# cc2650.net
KiCad netlist of a schematic drawn in EAGLE
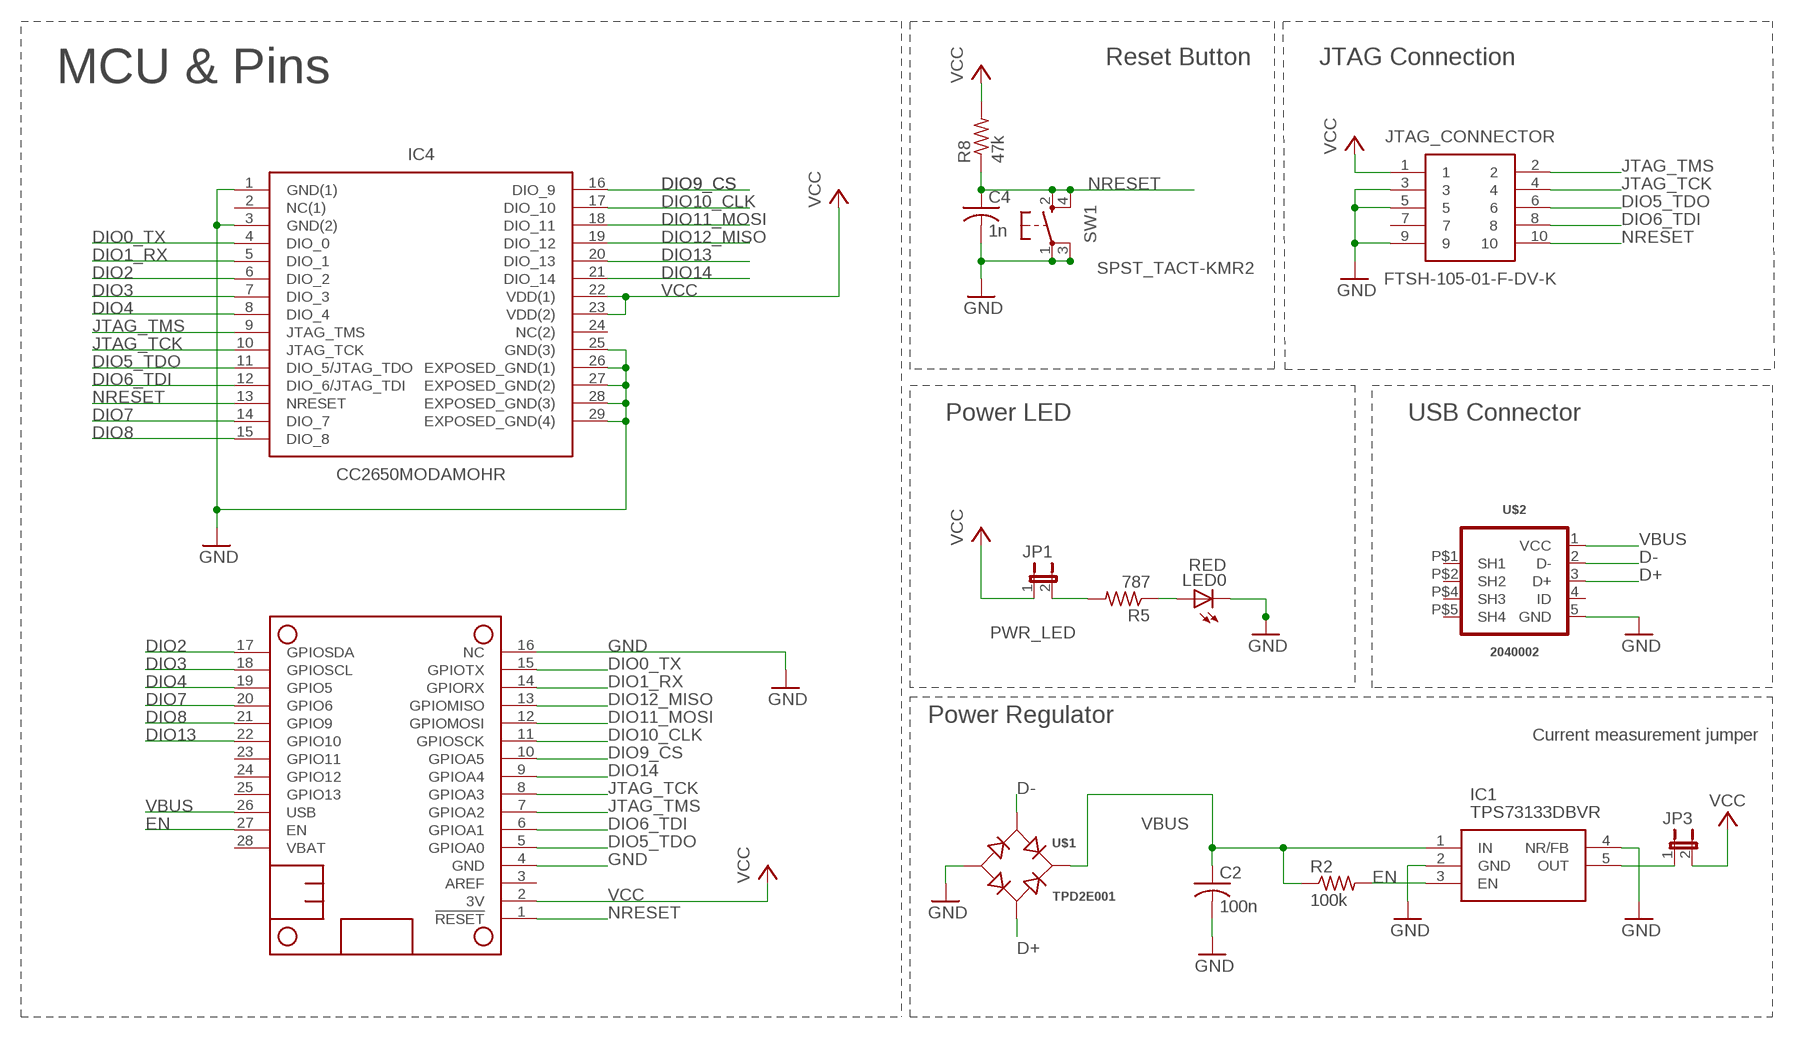
[diagram p0: schematic, sheet 1]
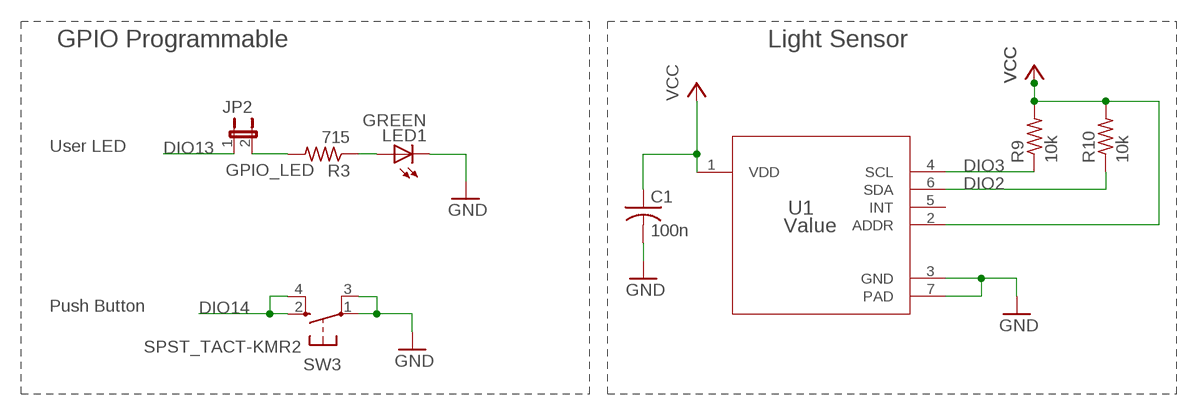
[diagram p1: schematic, sheet 2]

(export (version "E")
  (design (tool "Eeschema 10.0.6"))
  (components
    (comp (ref "C1")
      (value "100n")
      (footprint "eagle-import:C0805")
      (fields (field (name "MPN") "C0805C105K5RACTU"))
      (libsource (lib "eagle-import") (part "C-USC0805"))
    )
    (comp (ref "JP2")
      (value "GPIO_LED")
      (footprint "eagle-import:JP1M")
      (fields (field (name "MPN") "2211S-02G"))
      (libsource (lib "eagle-import") (part "JP1M"))
    )
    (comp (ref "LED1")
      (value "GREEN")
      (footprint "eagle-import:CHIPLED_0603")
      (libsource (lib "eagle-import") (part "LEDCHIPLED_0603"))
    )
    (comp (ref "R3")
      (value "715")
      (footprint "eagle-import:R0603")
      (fields (field (name "MPN") "RC0603JR-07100KL"))
      (libsource (lib "eagle-import") (part "R-US_R0603"))
    )
    (comp (ref "R9")
      (value "10k")
      (footprint "eagle-import:R1206")
      (libsource (lib "eagle-import") (part "R-US_R1206"))
    )
    (comp (ref "R10")
      (value "10k")
      (footprint "eagle-import:R1206")
      (libsource (lib "eagle-import") (part "R-US_R1206"))
    )
    (comp (ref "SW3")
      (value "SPST_TACT-KMR2")
      (footprint "eagle-import:KMR2")
      (fields (field (name "MPN") "KMR241G LFS"))
      (libsource (lib "eagle-import") (part "SPST_TACT-KMR2"))
    )
    (comp (ref "U1")
      (value "Value")
      (footprint "eagle-import:DNP0006A")
      (fields (field (name "MANUFACTURER") "Texas Instruments") (field (name "PARTNUMBER") "OPT3001DNP"))
      (libsource (lib "eagle-import") (part "OPT3001DNPR"))
    )
    (comp (ref "C2")
      (value "100n")
      (footprint "eagle-import:C1206")
      (libsource (lib "eagle-import") (part "C-USC1206"))
    )
    (comp (ref "C4")
      (value "1n")
      (footprint "eagle-import:C1206")
      (libsource (lib "eagle-import") (part "C-USC1206"))
    )
    (comp (ref "IC1")
      (value "TPS73133DBVR")
      (footprint "eagle-import:SOT95P280X145-5N")
      (fields (field (name "RS_PART_NUMBER") "6613970"))
      (libsource (lib "eagle-import") (part "TPS73133DBVR"))
    )
    (comp (ref "IC4")
      (value "CC2650MODAMOHR")
      (footprint "eagle-import:MOH0029A")
      (libsource (lib "eagle-import") (part "CC2650MODAMOHR"))
    )
    (comp (ref "JP1")
      (value "PWR_LED")
      (footprint "eagle-import:JP1M")
      (fields (field (name "MPN") "2211S-02G"))
      (libsource (lib "eagle-import") (part "JP1M"))
    )
    (comp (ref "JP3")
      (value "PWR_LED")
      (footprint "eagle-import:JP1M")
      (fields (field (name "MPN") "2211S-02G"))
      (libsource (lib "eagle-import") (part "JP1M"))
    )
    (comp (ref "JTAG_CONNECTOR")
      (value "FTSH-105-01-F-DV-K")
      (footprint "eagle-import:SAMTEC_FTSH-105-01-L-DV")
      (libsource (lib "eagle-import") (part "FTSH-105-01-F-DV-K"))
    )
    (comp (ref "LED0")
      (value "RED")
      (footprint "eagle-import:CHIPLED_0603")
      (libsource (lib "eagle-import") (part "LEDCHIPLED_0603"))
    )
    (comp (ref "MS1")
      (value "FEATHERWING_NODIM")
      (footprint "eagle-import:FEATHERWING_DIM")
      (libsource (lib "eagle-import") (part "FEATHERWING_NODIM"))
    )
    (comp (ref "R2")
      (value "100k")
      (footprint "eagle-import:R1206")
      (libsource (lib "eagle-import") (part "R-US_R1206"))
    )
    (comp (ref "R5")
      (value "787")
      (footprint "eagle-import:R0603")
      (fields (field (name "MPN") "RC0603JR-07100KL"))
      (libsource (lib "eagle-import") (part "R-US_R0603"))
    )
    (comp (ref "R8")
      (value "47k")
      (footprint "eagle-import:R1206")
      (libsource (lib "eagle-import") (part "R-US_R1206"))
    )
    (comp (ref "SW1")
      (value "SPST_TACT-KMR2")
      (footprint "eagle-import:KMR2")
      (fields (field (name "MPN") "KMR241G LFS"))
      (libsource (lib "eagle-import") (part "SPST_TACT-KMR2"))
    )
    (comp (ref "U$1")
      (value "TPD2E001")
      (footprint "eagle-import:SOT-143")
      (libsource (lib "eagle-import") (part "TPD2E001"))
    )
    (comp (ref "U$2")
      (value "2040002")
      (footprint "eagle-import:2040002")
      (libsource (lib "eagle-import") (part "2040002"))
    )
  )
  (nets
    (net (code "1") (name "D+") (class "Default")
      (node (ref "U$1") (pin "3") (pinfunction "AC2_3") (pintype "passive"))
      (node (ref "U$2") (pin "3") (pinfunction "D+_3") (pintype "bidirectional"))
    )
    (net (code "2") (name "D-") (class "Default")
      (node (ref "U$1") (pin "2") (pinfunction "AC1_2") (pintype "passive"))
      (node (ref "U$2") (pin "2") (pinfunction "D-_2") (pintype "bidirectional"))
    )
    (net (code "3") (name "DIO0_TX") (class "Default")
      (node (ref "IC4") (pin "4") (pinfunction "DIO_0_4") (pintype "passive"))
      (node (ref "MS1") (pin "15") (pinfunction "GPIOTX_15") (pintype "bidirectional"))
    )
    (net (code "4") (name "DIO1_RX") (class "Default")
      (node (ref "IC4") (pin "5") (pinfunction "DIO_1_5") (pintype "passive"))
      (node (ref "MS1") (pin "14") (pinfunction "GPIORX_14") (pintype "bidirectional"))
    )
    (net (code "5") (name "DIO2") (class "Default")
      (node (ref "IC4") (pin "6") (pinfunction "DIO_2_6") (pintype "passive"))
      (node (ref "MS1") (pin "17") (pinfunction "GPIOSDA_17") (pintype "bidirectional"))
      (node (ref "R10") (pin "1") (pinfunction "1_1") (pintype "passive"))
      (node (ref "U1") (pin "6") (pinfunction "SDA_6") (pintype "input"))
    )
    (net (code "6") (name "DIO3") (class "Default")
      (node (ref "IC4") (pin "7") (pinfunction "DIO_3_7") (pintype "passive"))
      (node (ref "MS1") (pin "18") (pinfunction "GPIOSCL_18") (pintype "bidirectional"))
      (node (ref "R9") (pin "1") (pinfunction "1_1") (pintype "passive"))
      (node (ref "U1") (pin "4") (pinfunction "SCL_4") (pintype "input"))
    )
    (net (code "7") (name "DIO4") (class "Default")
      (node (ref "IC4") (pin "8") (pinfunction "DIO_4_8") (pintype "passive"))
      (node (ref "MS1") (pin "19") (pinfunction "GPIO5_19") (pintype "bidirectional"))
    )
    (net (code "8") (name "DIO5_TDO") (class "Default")
      (node (ref "IC4") (pin "11") (pinfunction "DIO_5/JTAG_TDO_11") (pintype "passive"))
      (node (ref "JTAG_CONNECTOR") (pin "6") (pinfunction "6_6") (pintype "passive"))
      (node (ref "MS1") (pin "5") (pinfunction "GPIOA0_5") (pintype "bidirectional"))
    )
    (net (code "9") (name "DIO6_TDI") (class "Default")
      (node (ref "IC4") (pin "12") (pinfunction "DIO_6/JTAG_TDI_12") (pintype "passive"))
      (node (ref "JTAG_CONNECTOR") (pin "8") (pinfunction "8_8") (pintype "passive"))
      (node (ref "MS1") (pin "6") (pinfunction "GPIOA1_6") (pintype "bidirectional"))
    )
    (net (code "10") (name "DIO7") (class "Default")
      (node (ref "IC4") (pin "14") (pinfunction "DIO_7_14") (pintype "passive"))
      (node (ref "MS1") (pin "20") (pinfunction "GPIO6_20") (pintype "bidirectional"))
    )
    (net (code "11") (name "DIO8") (class "Default")
      (node (ref "IC4") (pin "15") (pinfunction "DIO_8_15") (pintype "passive"))
      (node (ref "MS1") (pin "21") (pinfunction "GPIO9_21") (pintype "bidirectional"))
    )
    (net (code "12") (name "DIO9_CS") (class "Default")
      (node (ref "IC4") (pin "16") (pinfunction "DIO_9_16") (pintype "passive"))
      (node (ref "MS1") (pin "10") (pinfunction "GPIOA5_10") (pintype "bidirectional"))
    )
    (net (code "13") (name "DIO10_CLK") (class "Default")
      (node (ref "IC4") (pin "17") (pinfunction "DIO_10_17") (pintype "passive"))
      (node (ref "MS1") (pin "11") (pinfunction "GPIOSCK_11") (pintype "bidirectional"))
    )
    (net (code "14") (name "DIO11_MOSI") (class "Default")
      (node (ref "IC4") (pin "18") (pinfunction "DIO_11_18") (pintype "passive"))
      (node (ref "MS1") (pin "12") (pinfunction "GPIOMOSI_12") (pintype "bidirectional"))
    )
    (net (code "15") (name "DIO12_MISO") (class "Default")
      (node (ref "IC4") (pin "19") (pinfunction "DIO_12_19") (pintype "passive"))
      (node (ref "MS1") (pin "13") (pinfunction "GPIOMISO_13") (pintype "bidirectional"))
    )
    (net (code "16") (name "DIO13") (class "Default")
      (node (ref "IC4") (pin "20") (pinfunction "DIO_13_20") (pintype "passive"))
      (node (ref "JP2") (pin "1") (pinfunction "1_1") (pintype "passive"))
      (node (ref "MS1") (pin "22") (pinfunction "GPIO10_22") (pintype "bidirectional"))
    )
    (net (code "17") (name "DIO14") (class "Default")
      (node (ref "IC4") (pin "21") (pinfunction "DIO_14_21") (pintype "passive"))
      (node (ref "MS1") (pin "9") (pinfunction "GPIOA4_9") (pintype "bidirectional"))
      (node (ref "SW3") (pin "2") (pinfunction "S_2") (pintype "passive"))
      (node (ref "SW3") (pin "4") (pinfunction "S1_4") (pintype "passive"))
    )
    (net (code "18") (name "EN") (class "Default")
      (node (ref "IC1") (pin "3") (pinfunction "EN_3") (pintype "input"))
      (node (ref "MS1") (pin "27") (pinfunction "EN_27") (pintype "passive"))
      (node (ref "R2") (pin "2") (pinfunction "2_2") (pintype "passive"))
    )
    (net (code "19") (name "GND") (class "Default")
      (node (ref "C1") (pin "2") (pinfunction "2_2") (pintype "passive"))
      (node (ref "C2") (pin "2") (pinfunction "2_2") (pintype "passive"))
      (node (ref "C4") (pin "2") (pinfunction "2_2") (pintype "passive"))
      (node (ref "IC1") (pin "2") (pinfunction "GND_2") (pintype "input"))
      (node (ref "IC1") (pin "4") (pinfunction "NR/FB_4") (pintype "input"))
      (node (ref "IC4") (pin "1") (pinfunction "GND(1)_1") (pintype "passive"))
      (node (ref "IC4") (pin "25") (pinfunction "GND(3)_25") (pintype "passive"))
      (node (ref "IC4") (pin "26") (pinfunction "EXPOSED_GND(1)_26") (pintype "passive"))
      (node (ref "IC4") (pin "27") (pinfunction "EXPOSED_GND(2)_27") (pintype "passive"))
      (node (ref "IC4") (pin "28") (pinfunction "EXPOSED_GND(3)_28") (pintype "passive"))
      (node (ref "IC4") (pin "29") (pinfunction "EXPOSED_GND(4)_29") (pintype "passive"))
      (node (ref "IC4") (pin "3") (pinfunction "GND(2)_3") (pintype "passive"))
      (node (ref "JTAG_CONNECTOR") (pin "3") (pinfunction "3_3") (pintype "passive"))
      (node (ref "JTAG_CONNECTOR") (pin "5") (pinfunction "5_5") (pintype "passive"))
      (node (ref "JTAG_CONNECTOR") (pin "9") (pinfunction "9_9") (pintype "passive"))
      (node (ref "LED0") (pin "C") (pinfunction "C_C") (pintype "passive"))
      (node (ref "LED1") (pin "C") (pinfunction "C_C") (pintype "passive"))
      (node (ref "MS1") (pin "16") (pinfunction "NC_16") (pintype "passive"))
      (node (ref "MS1") (pin "4") (pinfunction "GND_4") (pintype "power_in"))
      (node (ref "SW1") (pin "1") (pinfunction "P_1") (pintype "passive"))
      (node (ref "SW1") (pin "3") (pinfunction "P1_3") (pintype "passive"))
      (node (ref "SW3") (pin "1") (pinfunction "P_1") (pintype "passive"))
      (node (ref "SW3") (pin "3") (pinfunction "P1_3") (pintype "passive"))
      (node (ref "U$1") (pin "1") (pinfunction "-_1") (pintype "passive"))
      (node (ref "U$2") (pin "5") (pinfunction "GND_5") (pintype "bidirectional"))
      (node (ref "U1") (pin "3") (pinfunction "GND_3") (pintype "power_in"))
      (node (ref "U1") (pin "7") (pinfunction "PAD_7") (pintype "passive"))
    )
    (net (code "20") (name "JTAG_TCK") (class "Default")
      (node (ref "IC4") (pin "10") (pinfunction "JTAG_TCK_10") (pintype "passive"))
      (node (ref "JTAG_CONNECTOR") (pin "4") (pinfunction "4_4") (pintype "passive"))
      (node (ref "MS1") (pin "8") (pinfunction "GPIOA3_8") (pintype "bidirectional"))
    )
    (net (code "21") (name "JTAG_TMS") (class "Default")
      (node (ref "IC4") (pin "9") (pinfunction "JTAG_TMS_9") (pintype "passive"))
      (node (ref "JTAG_CONNECTOR") (pin "2") (pinfunction "2_2") (pintype "passive"))
      (node (ref "MS1") (pin "7") (pinfunction "GPIOA2_7") (pintype "bidirectional"))
    )
    (net (code "22") (name "NRESET") (class "Default")
      (node (ref "C4") (pin "1") (pinfunction "1_1") (pintype "passive"))
      (node (ref "IC4") (pin "13") (pinfunction "NRESET_13") (pintype "passive"))
      (node (ref "JTAG_CONNECTOR") (pin "10") (pinfunction "10_10") (pintype "passive"))
      (node (ref "MS1") (pin "1") (pinfunction "~{RESET}_1") (pintype "input"))
      (node (ref "R8") (pin "1") (pinfunction "1_1") (pintype "passive"))
      (node (ref "SW1") (pin "2") (pinfunction "S_2") (pintype "passive"))
      (node (ref "SW1") (pin "4") (pinfunction "S1_4") (pintype "passive"))
    )
    (net (code "23") (name "Net-(IC1-OUT)") (class "Default")
      (node (ref "IC1") (pin "5") (pinfunction "OUT_5") (pintype "input"))
      (node (ref "JP3") (pin "1") (pinfunction "1_1") (pintype "passive"))
    )
    (net (code "24") (name "Net-(JP1-Pad2)") (class "Default")
      (node (ref "JP1") (pin "2") (pinfunction "2_2") (pintype "passive"))
      (node (ref "R5") (pin "2") (pinfunction "2_2") (pintype "passive"))
    )
    (net (code "25") (name "Net-(JP2-Pad2)") (class "Default")
      (node (ref "JP2") (pin "2") (pinfunction "2_2") (pintype "passive"))
      (node (ref "R3") (pin "2") (pinfunction "2_2") (pintype "passive"))
    )
    (net (code "26") (name "Net-(LED0-PadA)") (class "Default")
      (node (ref "LED0") (pin "A") (pinfunction "A_A") (pintype "passive"))
      (node (ref "R5") (pin "1") (pinfunction "1_1") (pintype "passive"))
    )
    (net (code "27") (name "Net-(LED1-PadA)") (class "Default")
      (node (ref "LED1") (pin "A") (pinfunction "A_A") (pintype "passive"))
      (node (ref "R3") (pin "1") (pinfunction "1_1") (pintype "passive"))
    )
    (net (code "28") (name "VBAT") (class "Default")
      (node (ref "MS1") (pin "28") (pinfunction "VBAT_28") (pintype "power_in"))
    )
    (net (code "29") (name "VBUS") (class "Default")
      (node (ref "C2") (pin "1") (pinfunction "1_1") (pintype "passive"))
      (node (ref "IC1") (pin "1") (pinfunction "IN_1") (pintype "input"))
      (node (ref "MS1") (pin "26") (pinfunction "USB_26") (pintype "power_in"))
      (node (ref "R2") (pin "1") (pinfunction "1_1") (pintype "passive"))
      (node (ref "U$1") (pin "4") (pinfunction "+_4") (pintype "passive"))
      (node (ref "U$2") (pin "1") (pinfunction "VCC_1") (pintype "bidirectional"))
    )
    (net (code "30") (name "VCC") (class "Default")
      (node (ref "C1") (pin "1") (pinfunction "1_1") (pintype "passive"))
      (node (ref "IC4") (pin "22") (pinfunction "VDD(1)_22") (pintype "passive"))
      (node (ref "IC4") (pin "23") (pinfunction "VDD(2)_23") (pintype "passive"))
      (node (ref "JP1") (pin "1") (pinfunction "1_1") (pintype "passive"))
      (node (ref "JP3") (pin "2") (pinfunction "2_2") (pintype "passive"))
      (node (ref "JTAG_CONNECTOR") (pin "1") (pinfunction "1_1") (pintype "passive"))
      (node (ref "MS1") (pin "2") (pinfunction "3V_2") (pintype "power_in"))
      (node (ref "R10") (pin "2") (pinfunction "2_2") (pintype "passive"))
      (node (ref "R8") (pin "2") (pinfunction "2_2") (pintype "passive"))
      (node (ref "R9") (pin "2") (pinfunction "2_2") (pintype "passive"))
      (node (ref "U1") (pin "1") (pinfunction "VDD_1") (pintype "power_in"))
      (node (ref "U1") (pin "2") (pinfunction "ADDR_2") (pintype "input"))
    )
    (net (code "31") (name "unconnected-(IC4-NC(1)-Pad2)") (class "Default")
      (node (ref "IC4") (pin "2") (pinfunction "NC(1)_2") (pintype "passive"))
    )
    (net (code "32") (name "unconnected-(IC4-NC(2)-Pad24)") (class "Default")
      (node (ref "IC4") (pin "24") (pinfunction "NC(2)_24") (pintype "passive"))
    )
    (net (code "33") (name "unconnected-(JTAG_CONNECTOR-Pad7)") (class "Default")
      (node (ref "JTAG_CONNECTOR") (pin "7") (pinfunction "7_7") (pintype "passive"))
    )
    (net (code "34") (name "unconnected-(MS1-AREF-Pad3)") (class "Default")
      (node (ref "MS1") (pin "3") (pinfunction "AREF_3") (pintype "passive"))
    )
    (net (code "35") (name "unconnected-(MS1-GPIO11-Pad23)") (class "Default")
      (node (ref "MS1") (pin "23") (pinfunction "GPIO11_23") (pintype "bidirectional"))
    )
    (net (code "36") (name "unconnected-(MS1-GPIO12-Pad24)") (class "Default")
      (node (ref "MS1") (pin "24") (pinfunction "GPIO12_24") (pintype "bidirectional"))
    )
    (net (code "37") (name "unconnected-(MS1-GPIO13-Pad25)") (class "Default")
      (node (ref "MS1") (pin "25") (pinfunction "GPIO13_25") (pintype "bidirectional"))
    )
    (net (code "38") (name "unconnected-(U$2-ID-Pad4)") (class "Default")
      (node (ref "U$2") (pin "4") (pinfunction "ID_4") (pintype "bidirectional"))
    )
    (net (code "39") (name "unconnected-(U$2-SH1-PadP$1)") (class "Default")
      (node (ref "U$2") (pin "P$1") (pinfunction "SH1_P$1") (pintype "no_connect"))
    )
    (net (code "40") (name "unconnected-(U$2-SH2-PadP$2)") (class "Default")
      (node (ref "U$2") (pin "P$2") (pinfunction "SH2_P$2") (pintype "no_connect"))
    )
    (net (code "41") (name "unconnected-(U$2-SH3-PadP$4)") (class "Default")
      (node (ref "U$2") (pin "P$4") (pinfunction "SH3_P$4") (pintype "no_connect"))
    )
    (net (code "42") (name "unconnected-(U$2-SH4-PadP$5)") (class "Default")
      (node (ref "U$2") (pin "P$5") (pinfunction "SH4_P$5") (pintype "no_connect"))
    )
    (net (code "43") (name "unconnected-(U1-INT-Pad5)") (class "Default")
      (node (ref "U1") (pin "5") (pinfunction "INT_5") (pintype "output"))
    )
  )
)
